# Insoladora.net
KiCad netlist of a schematic drawn in EAGLE
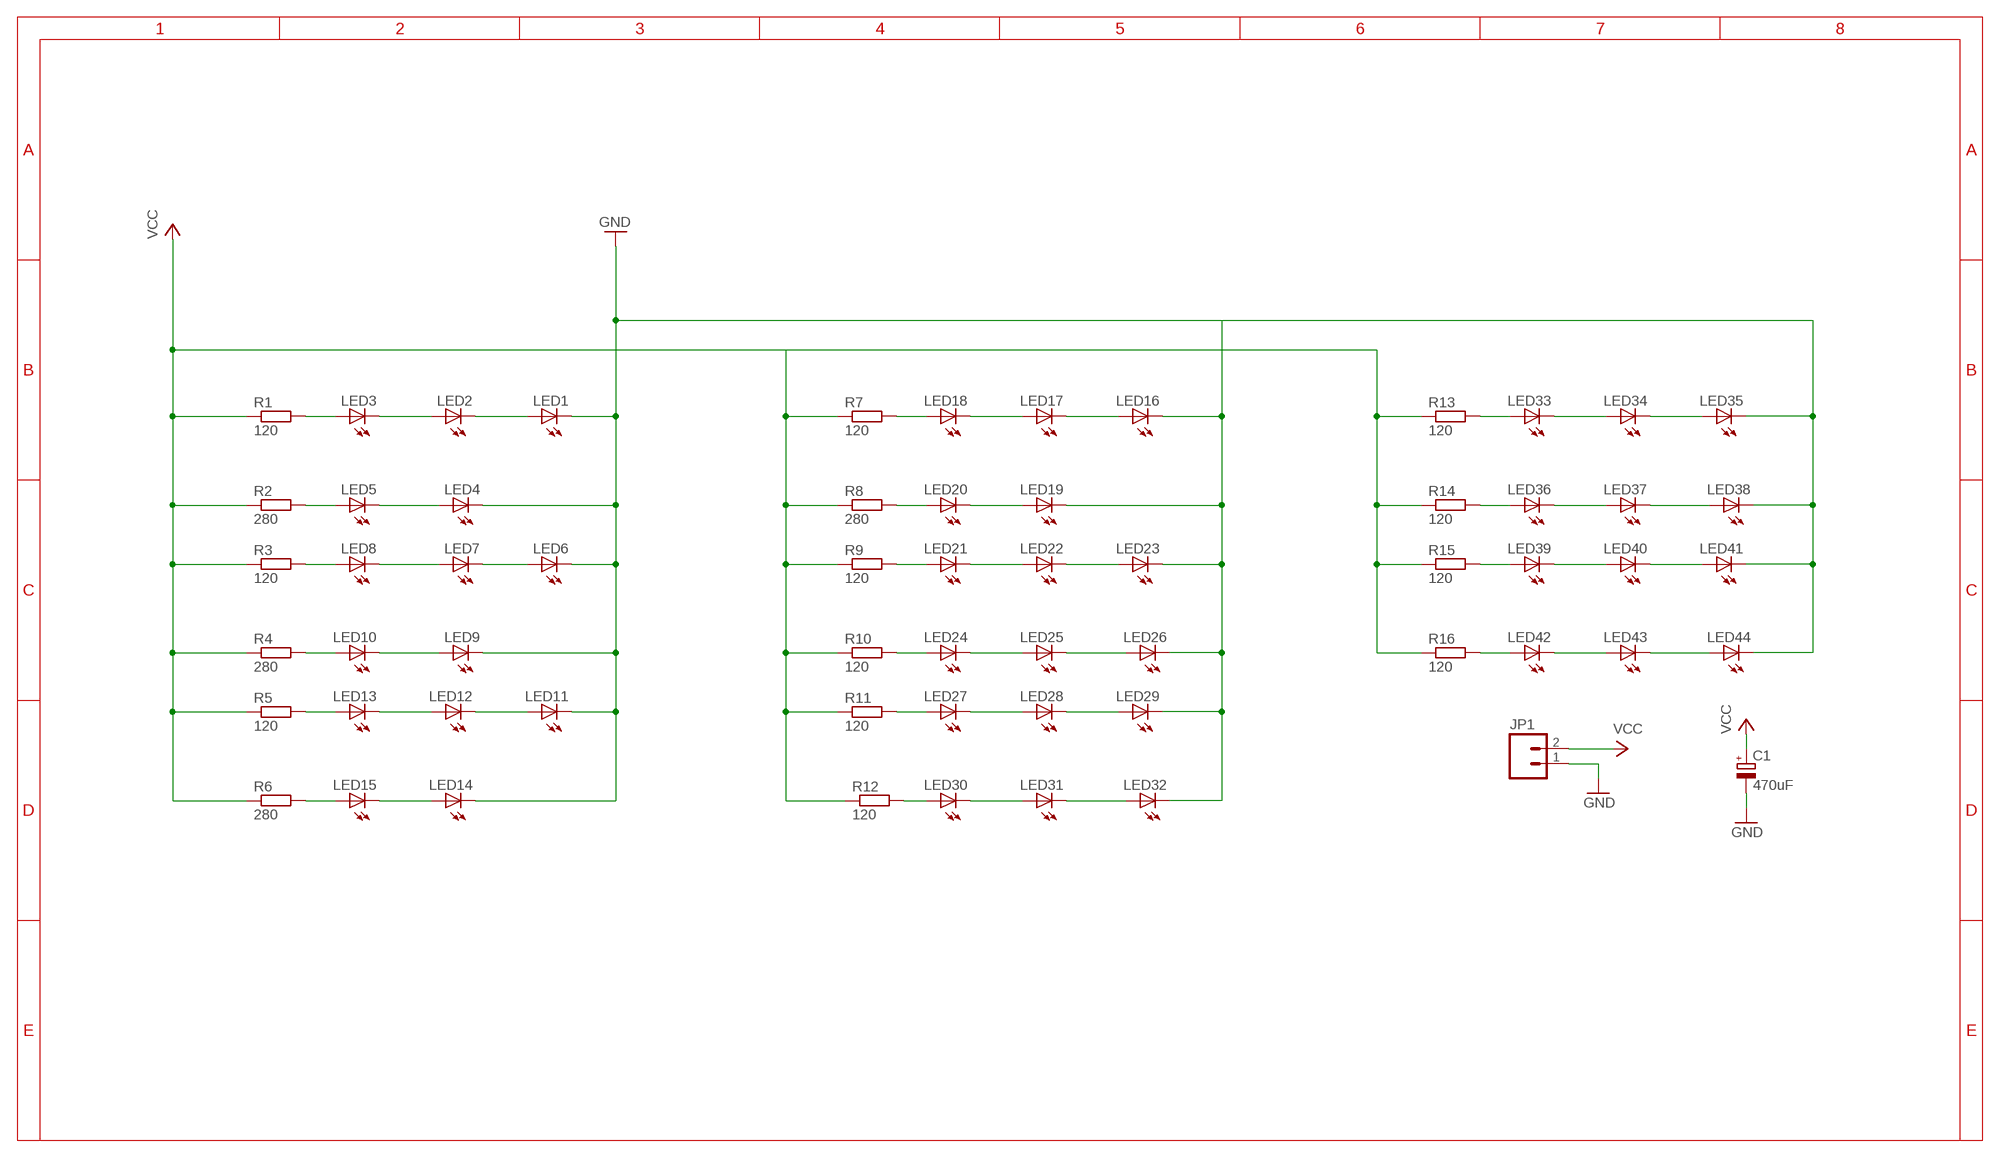
[diagram p0: schematic, sheet 1]

(export (version "E")
  (design (tool "Eeschema 10.0.6"))
  (components
    (comp (ref "C1")
      (value "470uF")
      (footprint "eagle-import:E2,5-7")
      (libsource (lib "eagle-import") (part "CPOL-EUE2.5-7"))
    )
    (comp (ref "JP1")
      (value "M023.5MM_LOCK")
      (footprint "eagle-import:SCREWTERMINAL-3.5MM-2_LOCK")
      (libsource (lib "eagle-import") (part "M023.5MM_LOCK"))
    )
    (comp (ref "LED1")
      (value "LED5MM")
      (footprint "eagle-import:LED5MM")
      (libsource (lib "eagle-import") (part "LED5MM"))
    )
    (comp (ref "LED2")
      (value "LED5MM")
      (footprint "eagle-import:LED5MM")
      (libsource (lib "eagle-import") (part "LED5MM"))
    )
    (comp (ref "LED3")
      (value "LED5MM")
      (footprint "eagle-import:LED5MM")
      (libsource (lib "eagle-import") (part "LED5MM"))
    )
    (comp (ref "LED4")
      (value "LED5MM")
      (footprint "eagle-import:LED5MM")
      (libsource (lib "eagle-import") (part "LED5MM"))
    )
    (comp (ref "LED5")
      (value "LED5MM")
      (footprint "eagle-import:LED5MM")
      (libsource (lib "eagle-import") (part "LED5MM"))
    )
    (comp (ref "LED6")
      (value "LED5MM")
      (footprint "eagle-import:LED5MM")
      (libsource (lib "eagle-import") (part "LED5MM"))
    )
    (comp (ref "LED7")
      (value "LED5MM")
      (footprint "eagle-import:LED5MM")
      (libsource (lib "eagle-import") (part "LED5MM"))
    )
    (comp (ref "LED8")
      (value "LED5MM")
      (footprint "eagle-import:LED5MM")
      (libsource (lib "eagle-import") (part "LED5MM"))
    )
    (comp (ref "LED9")
      (value "LED5MM")
      (footprint "eagle-import:LED5MM")
      (libsource (lib "eagle-import") (part "LED5MM"))
    )
    (comp (ref "LED10")
      (value "LED5MM")
      (footprint "eagle-import:LED5MM")
      (libsource (lib "eagle-import") (part "LED5MM"))
    )
    (comp (ref "LED11")
      (value "LED5MM")
      (footprint "eagle-import:LED5MM")
      (libsource (lib "eagle-import") (part "LED5MM"))
    )
    (comp (ref "LED12")
      (value "LED5MM")
      (footprint "eagle-import:LED5MM")
      (libsource (lib "eagle-import") (part "LED5MM"))
    )
    (comp (ref "LED13")
      (value "LED5MM")
      (footprint "eagle-import:LED5MM")
      (libsource (lib "eagle-import") (part "LED5MM"))
    )
    (comp (ref "LED14")
      (value "LED5MM")
      (footprint "eagle-import:LED5MM")
      (libsource (lib "eagle-import") (part "LED5MM"))
    )
    (comp (ref "LED15")
      (value "LED5MM")
      (footprint "eagle-import:LED5MM")
      (libsource (lib "eagle-import") (part "LED5MM"))
    )
    (comp (ref "LED16")
      (value "LED5MM")
      (footprint "eagle-import:LED5MM")
      (libsource (lib "eagle-import") (part "LED5MM"))
    )
    (comp (ref "LED17")
      (value "LED5MM")
      (footprint "eagle-import:LED5MM")
      (libsource (lib "eagle-import") (part "LED5MM"))
    )
    (comp (ref "LED18")
      (value "LED5MM")
      (footprint "eagle-import:LED5MM")
      (libsource (lib "eagle-import") (part "LED5MM"))
    )
    (comp (ref "LED19")
      (value "LED5MM")
      (footprint "eagle-import:LED5MM")
      (libsource (lib "eagle-import") (part "LED5MM"))
    )
    (comp (ref "LED20")
      (value "LED5MM")
      (footprint "eagle-import:LED5MM")
      (libsource (lib "eagle-import") (part "LED5MM"))
    )
    (comp (ref "LED21")
      (value "LED5MM")
      (footprint "eagle-import:LED5MM")
      (libsource (lib "eagle-import") (part "LED5MM"))
    )
    (comp (ref "LED22")
      (value "LED5MM")
      (footprint "eagle-import:LED5MM")
      (libsource (lib "eagle-import") (part "LED5MM"))
    )
    (comp (ref "LED23")
      (value "LED5MM")
      (footprint "eagle-import:LED5MM")
      (libsource (lib "eagle-import") (part "LED5MM"))
    )
    (comp (ref "LED24")
      (value "LED5MM")
      (footprint "eagle-import:LED5MM")
      (libsource (lib "eagle-import") (part "LED5MM"))
    )
    (comp (ref "LED25")
      (value "LED5MM")
      (footprint "eagle-import:LED5MM")
      (libsource (lib "eagle-import") (part "LED5MM"))
    )
    (comp (ref "LED26")
      (value "LED5MM")
      (footprint "eagle-import:LED5MM")
      (libsource (lib "eagle-import") (part "LED5MM"))
    )
    (comp (ref "LED27")
      (value "LED5MM")
      (footprint "eagle-import:LED5MM")
      (libsource (lib "eagle-import") (part "LED5MM"))
    )
    (comp (ref "LED28")
      (value "LED5MM")
      (footprint "eagle-import:LED5MM")
      (libsource (lib "eagle-import") (part "LED5MM"))
    )
    (comp (ref "LED29")
      (value "LED5MM")
      (footprint "eagle-import:LED5MM")
      (libsource (lib "eagle-import") (part "LED5MM"))
    )
    (comp (ref "LED30")
      (value "LED5MM")
      (footprint "eagle-import:LED5MM")
      (libsource (lib "eagle-import") (part "LED5MM"))
    )
    (comp (ref "LED31")
      (value "LED5MM")
      (footprint "eagle-import:LED5MM")
      (libsource (lib "eagle-import") (part "LED5MM"))
    )
    (comp (ref "LED32")
      (value "LED5MM")
      (footprint "eagle-import:LED5MM")
      (libsource (lib "eagle-import") (part "LED5MM"))
    )
    (comp (ref "LED33")
      (value "LED5MM")
      (footprint "eagle-import:LED5MM")
      (libsource (lib "eagle-import") (part "LED5MM"))
    )
    (comp (ref "LED34")
      (value "LED5MM")
      (footprint "eagle-import:LED5MM")
      (libsource (lib "eagle-import") (part "LED5MM"))
    )
    (comp (ref "LED35")
      (value "LED5MM")
      (footprint "eagle-import:LED5MM")
      (libsource (lib "eagle-import") (part "LED5MM"))
    )
    (comp (ref "LED36")
      (value "LED5MM")
      (footprint "eagle-import:LED5MM")
      (libsource (lib "eagle-import") (part "LED5MM"))
    )
    (comp (ref "LED37")
      (value "LED5MM")
      (footprint "eagle-import:LED5MM")
      (libsource (lib "eagle-import") (part "LED5MM"))
    )
    (comp (ref "LED38")
      (value "LED5MM")
      (footprint "eagle-import:LED5MM")
      (libsource (lib "eagle-import") (part "LED5MM"))
    )
    (comp (ref "LED39")
      (value "LED5MM")
      (footprint "eagle-import:LED5MM")
      (libsource (lib "eagle-import") (part "LED5MM"))
    )
    (comp (ref "LED40")
      (value "LED5MM")
      (footprint "eagle-import:LED5MM")
      (libsource (lib "eagle-import") (part "LED5MM"))
    )
    (comp (ref "LED41")
      (value "LED5MM")
      (footprint "eagle-import:LED5MM")
      (libsource (lib "eagle-import") (part "LED5MM"))
    )
    (comp (ref "LED42")
      (value "LED5MM")
      (footprint "eagle-import:LED5MM")
      (libsource (lib "eagle-import") (part "LED5MM"))
    )
    (comp (ref "LED43")
      (value "LED5MM")
      (footprint "eagle-import:LED5MM")
      (libsource (lib "eagle-import") (part "LED5MM"))
    )
    (comp (ref "LED44")
      (value "LED5MM")
      (footprint "eagle-import:LED5MM")
      (libsource (lib "eagle-import") (part "LED5MM"))
    )
    (comp (ref "R1")
      (value "120")
      (footprint "eagle-import:0207_10")
      (libsource (lib "eagle-import") (part "R-EU_0207/10"))
    )
    (comp (ref "R2")
      (value "280")
      (footprint "eagle-import:0207_10")
      (libsource (lib "eagle-import") (part "R-EU_0207/10"))
    )
    (comp (ref "R3")
      (value "120")
      (footprint "eagle-import:0207_10")
      (libsource (lib "eagle-import") (part "R-EU_0207/10"))
    )
    (comp (ref "R4")
      (value "280")
      (footprint "eagle-import:0207_10")
      (libsource (lib "eagle-import") (part "R-EU_0207/10"))
    )
    (comp (ref "R5")
      (value "120")
      (footprint "eagle-import:0207_10")
      (libsource (lib "eagle-import") (part "R-EU_0207/10"))
    )
    (comp (ref "R6")
      (value "280")
      (footprint "eagle-import:0207_10")
      (libsource (lib "eagle-import") (part "R-EU_0207/10"))
    )
    (comp (ref "R7")
      (value "120")
      (footprint "eagle-import:0207_10")
      (libsource (lib "eagle-import") (part "R-EU_0207/10"))
    )
    (comp (ref "R8")
      (value "280")
      (footprint "eagle-import:0207_10")
      (libsource (lib "eagle-import") (part "R-EU_0207/10"))
    )
    (comp (ref "R9")
      (value "120")
      (footprint "eagle-import:0207_10")
      (libsource (lib "eagle-import") (part "R-EU_0207/10"))
    )
    (comp (ref "R10")
      (value "120")
      (footprint "eagle-import:0207_10")
      (libsource (lib "eagle-import") (part "R-EU_0207/10"))
    )
    (comp (ref "R11")
      (value "120")
      (footprint "eagle-import:0207_10")
      (libsource (lib "eagle-import") (part "R-EU_0207/10"))
    )
    (comp (ref "R12")
      (value "120")
      (footprint "eagle-import:0207_10")
      (libsource (lib "eagle-import") (part "R-EU_0207/10"))
    )
    (comp (ref "R13")
      (value "120")
      (footprint "eagle-import:0207_10")
      (libsource (lib "eagle-import") (part "R-EU_0207/10"))
    )
    (comp (ref "R14")
      (value "120")
      (footprint "eagle-import:0207_10")
      (libsource (lib "eagle-import") (part "R-EU_0207/10"))
    )
    (comp (ref "R15")
      (value "120")
      (footprint "eagle-import:0207_10")
      (libsource (lib "eagle-import") (part "R-EU_0207/10"))
    )
    (comp (ref "R16")
      (value "120")
      (footprint "eagle-import:0207_10")
      (libsource (lib "eagle-import") (part "R-EU_0207/10"))
    )
  )
  (nets
    (net (code "1") (name "GND") (class "Default")
      (node (ref "C1") (pin "-") (pinfunction "-_-") (pintype "passive"))
      (node (ref "JP1") (pin "1") (pinfunction "1_1") (pintype "passive"))
      (node (ref "LED1") (pin "K") (pinfunction "C_K") (pintype "passive"))
      (node (ref "LED11") (pin "K") (pinfunction "C_K") (pintype "passive"))
      (node (ref "LED14") (pin "K") (pinfunction "C_K") (pintype "passive"))
      (node (ref "LED16") (pin "K") (pinfunction "C_K") (pintype "passive"))
      (node (ref "LED19") (pin "K") (pinfunction "C_K") (pintype "passive"))
      (node (ref "LED23") (pin "K") (pinfunction "C_K") (pintype "passive"))
      (node (ref "LED26") (pin "K") (pinfunction "C_K") (pintype "passive"))
      (node (ref "LED29") (pin "K") (pinfunction "C_K") (pintype "passive"))
      (node (ref "LED32") (pin "K") (pinfunction "C_K") (pintype "passive"))
      (node (ref "LED35") (pin "K") (pinfunction "C_K") (pintype "passive"))
      (node (ref "LED38") (pin "K") (pinfunction "C_K") (pintype "passive"))
      (node (ref "LED4") (pin "K") (pinfunction "C_K") (pintype "passive"))
      (node (ref "LED41") (pin "K") (pinfunction "C_K") (pintype "passive"))
      (node (ref "LED44") (pin "K") (pinfunction "C_K") (pintype "passive"))
      (node (ref "LED6") (pin "K") (pinfunction "C_K") (pintype "passive"))
      (node (ref "LED9") (pin "K") (pinfunction "C_K") (pintype "passive"))
    )
    (net (code "2") (name "Net-(LED2-C)") (class "Default")
      (node (ref "LED1") (pin "A") (pinfunction "A_A") (pintype "passive"))
      (node (ref "LED2") (pin "K") (pinfunction "C_K") (pintype "passive"))
    )
    (net (code "3") (name "Net-(LED3-C)") (class "Default")
      (node (ref "LED2") (pin "A") (pinfunction "A_A") (pintype "passive"))
      (node (ref "LED3") (pin "K") (pinfunction "C_K") (pintype "passive"))
    )
    (net (code "4") (name "Net-(LED3-PadA)") (class "Default")
      (node (ref "LED3") (pin "A") (pinfunction "A_A") (pintype "passive"))
      (node (ref "R1") (pin "2") (pinfunction "2_2") (pintype "passive"))
    )
    (net (code "5") (name "Net-(LED5-C)") (class "Default")
      (node (ref "LED4") (pin "A") (pinfunction "A_A") (pintype "passive"))
      (node (ref "LED5") (pin "K") (pinfunction "C_K") (pintype "passive"))
    )
    (net (code "6") (name "Net-(LED5-PadA)") (class "Default")
      (node (ref "LED5") (pin "A") (pinfunction "A_A") (pintype "passive"))
      (node (ref "R2") (pin "2") (pinfunction "2_2") (pintype "passive"))
    )
    (net (code "7") (name "Net-(LED7-C)") (class "Default")
      (node (ref "LED6") (pin "A") (pinfunction "A_A") (pintype "passive"))
      (node (ref "LED7") (pin "K") (pinfunction "C_K") (pintype "passive"))
    )
    (net (code "8") (name "Net-(LED8-C)") (class "Default")
      (node (ref "LED7") (pin "A") (pinfunction "A_A") (pintype "passive"))
      (node (ref "LED8") (pin "K") (pinfunction "C_K") (pintype "passive"))
    )
    (net (code "9") (name "Net-(LED8-PadA)") (class "Default")
      (node (ref "LED8") (pin "A") (pinfunction "A_A") (pintype "passive"))
      (node (ref "R3") (pin "2") (pinfunction "2_2") (pintype "passive"))
    )
    (net (code "10") (name "Net-(LED10-C)") (class "Default")
      (node (ref "LED10") (pin "K") (pinfunction "C_K") (pintype "passive"))
      (node (ref "LED9") (pin "A") (pinfunction "A_A") (pintype "passive"))
    )
    (net (code "11") (name "Net-(LED10-PadA)") (class "Default")
      (node (ref "LED10") (pin "A") (pinfunction "A_A") (pintype "passive"))
      (node (ref "R4") (pin "2") (pinfunction "2_2") (pintype "passive"))
    )
    (net (code "12") (name "Net-(LED12-C)") (class "Default")
      (node (ref "LED11") (pin "A") (pinfunction "A_A") (pintype "passive"))
      (node (ref "LED12") (pin "K") (pinfunction "C_K") (pintype "passive"))
    )
    (net (code "13") (name "Net-(LED13-C)") (class "Default")
      (node (ref "LED12") (pin "A") (pinfunction "A_A") (pintype "passive"))
      (node (ref "LED13") (pin "K") (pinfunction "C_K") (pintype "passive"))
    )
    (net (code "14") (name "Net-(LED13-PadA)") (class "Default")
      (node (ref "LED13") (pin "A") (pinfunction "A_A") (pintype "passive"))
      (node (ref "R5") (pin "2") (pinfunction "2_2") (pintype "passive"))
    )
    (net (code "15") (name "Net-(LED15-C)") (class "Default")
      (node (ref "LED14") (pin "A") (pinfunction "A_A") (pintype "passive"))
      (node (ref "LED15") (pin "K") (pinfunction "C_K") (pintype "passive"))
    )
    (net (code "16") (name "Net-(LED15-PadA)") (class "Default")
      (node (ref "LED15") (pin "A") (pinfunction "A_A") (pintype "passive"))
      (node (ref "R6") (pin "2") (pinfunction "2_2") (pintype "passive"))
    )
    (net (code "17") (name "Net-(LED17-C)") (class "Default")
      (node (ref "LED16") (pin "A") (pinfunction "A_A") (pintype "passive"))
      (node (ref "LED17") (pin "K") (pinfunction "C_K") (pintype "passive"))
    )
    (net (code "18") (name "Net-(LED18-C)") (class "Default")
      (node (ref "LED17") (pin "A") (pinfunction "A_A") (pintype "passive"))
      (node (ref "LED18") (pin "K") (pinfunction "C_K") (pintype "passive"))
    )
    (net (code "19") (name "Net-(LED18-PadA)") (class "Default")
      (node (ref "LED18") (pin "A") (pinfunction "A_A") (pintype "passive"))
      (node (ref "R7") (pin "2") (pinfunction "2_2") (pintype "passive"))
    )
    (net (code "20") (name "Net-(LED20-C)") (class "Default")
      (node (ref "LED19") (pin "A") (pinfunction "A_A") (pintype "passive"))
      (node (ref "LED20") (pin "K") (pinfunction "C_K") (pintype "passive"))
    )
    (net (code "21") (name "Net-(LED20-PadA)") (class "Default")
      (node (ref "LED20") (pin "A") (pinfunction "A_A") (pintype "passive"))
      (node (ref "R8") (pin "2") (pinfunction "2_2") (pintype "passive"))
    )
    (net (code "22") (name "Net-(LED21-C)") (class "Default")
      (node (ref "LED21") (pin "K") (pinfunction "C_K") (pintype "passive"))
      (node (ref "LED22") (pin "A") (pinfunction "A_A") (pintype "passive"))
    )
    (net (code "23") (name "Net-(LED21-PadA)") (class "Default")
      (node (ref "LED21") (pin "A") (pinfunction "A_A") (pintype "passive"))
      (node (ref "R9") (pin "2") (pinfunction "2_2") (pintype "passive"))
    )
    (net (code "24") (name "Net-(LED22-C)") (class "Default")
      (node (ref "LED22") (pin "K") (pinfunction "C_K") (pintype "passive"))
      (node (ref "LED23") (pin "A") (pinfunction "A_A") (pintype "passive"))
    )
    (net (code "25") (name "Net-(LED24-C)") (class "Default")
      (node (ref "LED24") (pin "K") (pinfunction "C_K") (pintype "passive"))
      (node (ref "LED25") (pin "A") (pinfunction "A_A") (pintype "passive"))
    )
    (net (code "26") (name "Net-(LED24-PadA)") (class "Default")
      (node (ref "LED24") (pin "A") (pinfunction "A_A") (pintype "passive"))
      (node (ref "R10") (pin "2") (pinfunction "2_2") (pintype "passive"))
    )
    (net (code "27") (name "Net-(LED25-C)") (class "Default")
      (node (ref "LED25") (pin "K") (pinfunction "C_K") (pintype "passive"))
      (node (ref "LED26") (pin "A") (pinfunction "A_A") (pintype "passive"))
    )
    (net (code "28") (name "Net-(LED27-C)") (class "Default")
      (node (ref "LED27") (pin "K") (pinfunction "C_K") (pintype "passive"))
      (node (ref "LED28") (pin "A") (pinfunction "A_A") (pintype "passive"))
    )
    (net (code "29") (name "Net-(LED27-PadA)") (class "Default")
      (node (ref "LED27") (pin "A") (pinfunction "A_A") (pintype "passive"))
      (node (ref "R11") (pin "2") (pinfunction "2_2") (pintype "passive"))
    )
    (net (code "30") (name "Net-(LED28-C)") (class "Default")
      (node (ref "LED28") (pin "K") (pinfunction "C_K") (pintype "passive"))
      (node (ref "LED29") (pin "A") (pinfunction "A_A") (pintype "passive"))
    )
    (net (code "31") (name "Net-(LED30-C)") (class "Default")
      (node (ref "LED30") (pin "K") (pinfunction "C_K") (pintype "passive"))
      (node (ref "LED31") (pin "A") (pinfunction "A_A") (pintype "passive"))
    )
    (net (code "32") (name "Net-(LED30-PadA)") (class "Default")
      (node (ref "LED30") (pin "A") (pinfunction "A_A") (pintype "passive"))
      (node (ref "R12") (pin "2") (pinfunction "2_2") (pintype "passive"))
    )
    (net (code "33") (name "Net-(LED31-C)") (class "Default")
      (node (ref "LED31") (pin "K") (pinfunction "C_K") (pintype "passive"))
      (node (ref "LED32") (pin "A") (pinfunction "A_A") (pintype "passive"))
    )
    (net (code "34") (name "Net-(LED33-C)") (class "Default")
      (node (ref "LED33") (pin "K") (pinfunction "C_K") (pintype "passive"))
      (node (ref "LED34") (pin "A") (pinfunction "A_A") (pintype "passive"))
    )
    (net (code "35") (name "Net-(LED33-PadA)") (class "Default")
      (node (ref "LED33") (pin "A") (pinfunction "A_A") (pintype "passive"))
      (node (ref "R13") (pin "2") (pinfunction "2_2") (pintype "passive"))
    )
    (net (code "36") (name "Net-(LED34-C)") (class "Default")
      (node (ref "LED34") (pin "K") (pinfunction "C_K") (pintype "passive"))
      (node (ref "LED35") (pin "A") (pinfunction "A_A") (pintype "passive"))
    )
    (net (code "37") (name "Net-(LED36-C)") (class "Default")
      (node (ref "LED36") (pin "K") (pinfunction "C_K") (pintype "passive"))
      (node (ref "LED37") (pin "A") (pinfunction "A_A") (pintype "passive"))
    )
    (net (code "38") (name "Net-(LED36-PadA)") (class "Default")
      (node (ref "LED36") (pin "A") (pinfunction "A_A") (pintype "passive"))
      (node (ref "R14") (pin "2") (pinfunction "2_2") (pintype "passive"))
    )
    (net (code "39") (name "Net-(LED37-C)") (class "Default")
      (node (ref "LED37") (pin "K") (pinfunction "C_K") (pintype "passive"))
      (node (ref "LED38") (pin "A") (pinfunction "A_A") (pintype "passive"))
    )
    (net (code "40") (name "Net-(LED39-C)") (class "Default")
      (node (ref "LED39") (pin "K") (pinfunction "C_K") (pintype "passive"))
      (node (ref "LED40") (pin "A") (pinfunction "A_A") (pintype "passive"))
    )
    (net (code "41") (name "Net-(LED39-PadA)") (class "Default")
      (node (ref "LED39") (pin "A") (pinfunction "A_A") (pintype "passive"))
      (node (ref "R15") (pin "2") (pinfunction "2_2") (pintype "passive"))
    )
    (net (code "42") (name "Net-(LED40-C)") (class "Default")
      (node (ref "LED40") (pin "K") (pinfunction "C_K") (pintype "passive"))
      (node (ref "LED41") (pin "A") (pinfunction "A_A") (pintype "passive"))
    )
    (net (code "43") (name "Net-(LED42-C)") (class "Default")
      (node (ref "LED42") (pin "K") (pinfunction "C_K") (pintype "passive"))
      (node (ref "LED43") (pin "A") (pinfunction "A_A") (pintype "passive"))
    )
    (net (code "44") (name "Net-(LED42-PadA)") (class "Default")
      (node (ref "LED42") (pin "A") (pinfunction "A_A") (pintype "passive"))
      (node (ref "R16") (pin "2") (pinfunction "2_2") (pintype "passive"))
    )
    (net (code "45") (name "Net-(LED43-C)") (class "Default")
      (node (ref "LED43") (pin "K") (pinfunction "C_K") (pintype "passive"))
      (node (ref "LED44") (pin "A") (pinfunction "A_A") (pintype "passive"))
    )
    (net (code "46") (name "VCC") (class "Default")
      (node (ref "C1") (pin "+") (pinfunction "+_+") (pintype "passive"))
      (node (ref "JP1") (pin "2") (pinfunction "2_2") (pintype "passive"))
      (node (ref "R1") (pin "1") (pinfunction "1_1") (pintype "passive"))
      (node (ref "R10") (pin "1") (pinfunction "1_1") (pintype "passive"))
      (node (ref "R11") (pin "1") (pinfunction "1_1") (pintype "passive"))
      (node (ref "R12") (pin "1") (pinfunction "1_1") (pintype "passive"))
      (node (ref "R13") (pin "1") (pinfunction "1_1") (pintype "passive"))
      (node (ref "R14") (pin "1") (pinfunction "1_1") (pintype "passive"))
      (node (ref "R15") (pin "1") (pinfunction "1_1") (pintype "passive"))
      (node (ref "R16") (pin "1") (pinfunction "1_1") (pintype "passive"))
      (node (ref "R2") (pin "1") (pinfunction "1_1") (pintype "passive"))
      (node (ref "R3") (pin "1") (pinfunction "1_1") (pintype "passive"))
      (node (ref "R4") (pin "1") (pinfunction "1_1") (pintype "passive"))
      (node (ref "R5") (pin "1") (pinfunction "1_1") (pintype "passive"))
      (node (ref "R6") (pin "1") (pinfunction "1_1") (pintype "passive"))
      (node (ref "R7") (pin "1") (pinfunction "1_1") (pintype "passive"))
      (node (ref "R8") (pin "1") (pinfunction "1_1") (pintype "passive"))
      (node (ref "R9") (pin "1") (pinfunction "1_1") (pintype "passive"))
    )
  )
)
